# ProPrj_stm32G474_PPO_Display_2026-03-19.net
KiCad netlist of a schematic drawn in EasyEDA Pro
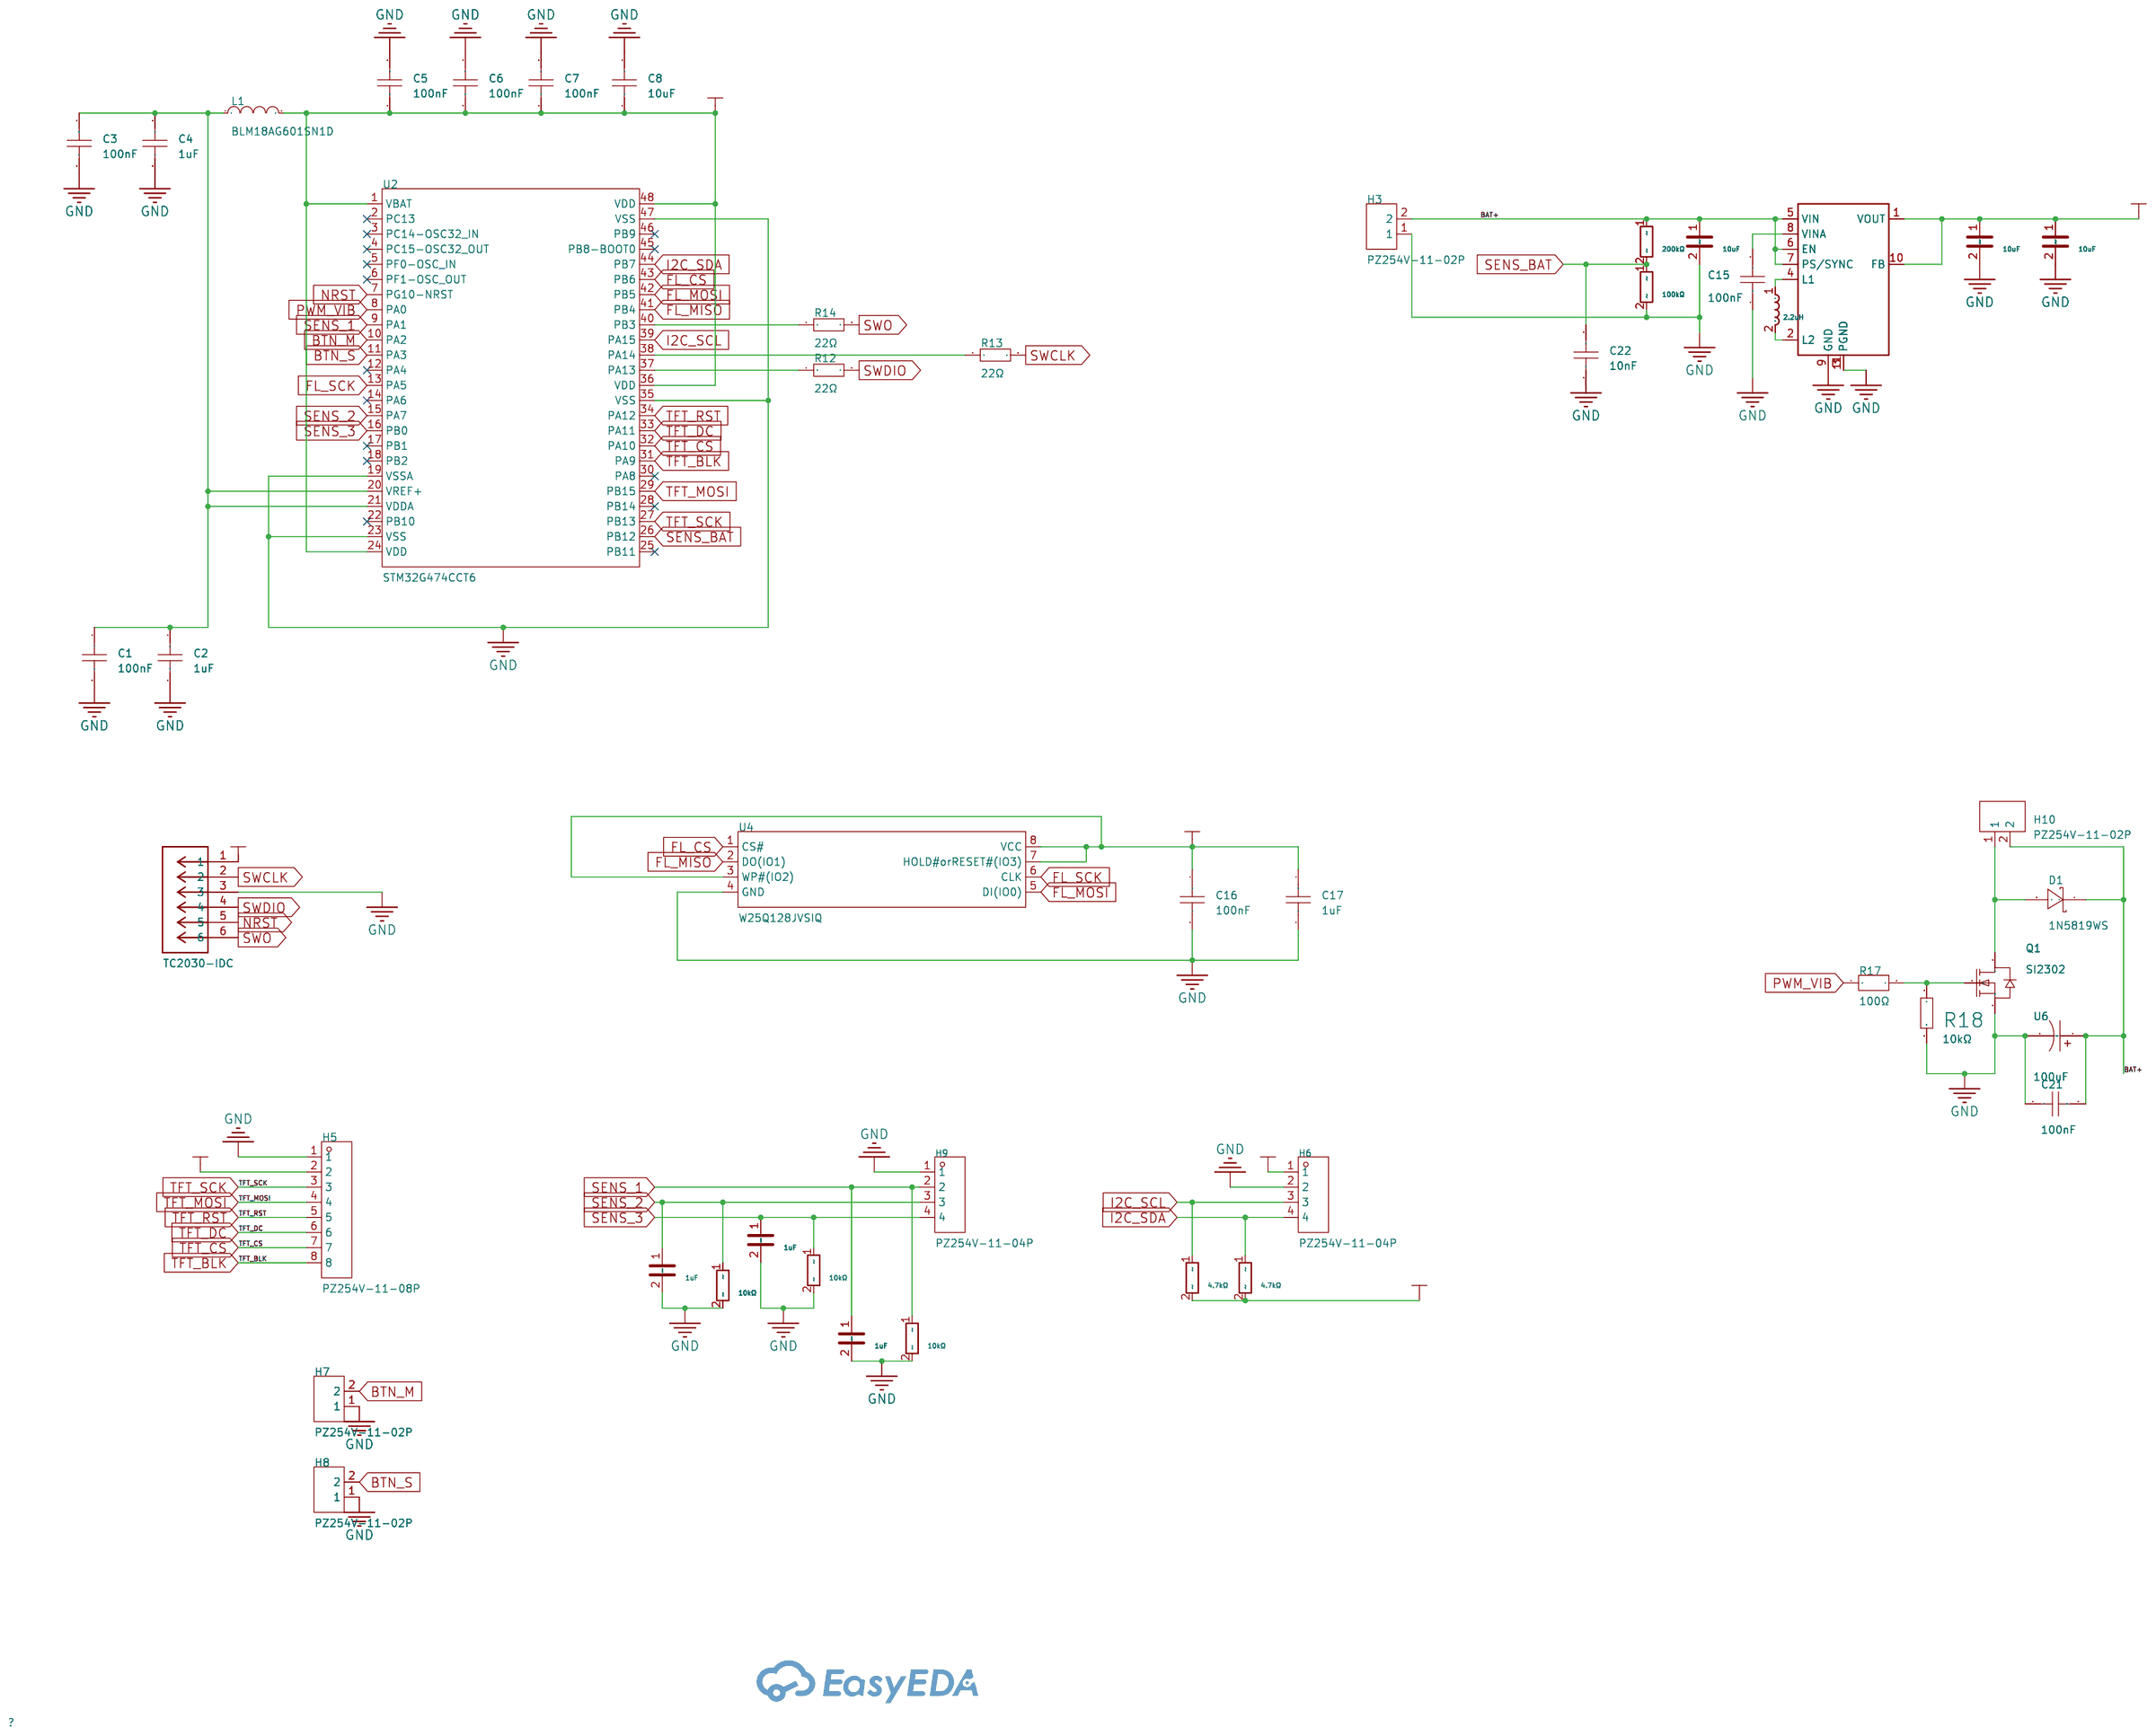
[diagram p0: schematic sheet]

(export (version "E")
  (design (tool "Eeschema 10.0.6"))
  (components
    (comp (ref "C1")
      (value "100nF")
      (footprint "easyedapro:C0603")
      (description "Capacitance:100nF Tolerance:±10% Tolerance:±10% Voltage Rating:50V Temperature Coefficient:X7R")
      (fields
        (field (name "Manufacturer Part") "CC0603KRX7R9BB104")
        (field (name "Manufacturer") "YAGEO(国巨)")
      )
      (libsource (lib "easyedapro") (part "CC0603KRX7R9BB104"))
    )
    (comp (ref "C2")
      (value "1uF")
      (footprint "easyedapro:C0603")
      (description "Capacitance:1uF Tolerance:±10% Tolerance:±10% Voltage Rating:50V Temperature Coefficient:X5R")
      (fields
        (field (name "Manufacturer Part") "CL10A105KB8NNNC")
        (field (name "Manufacturer") "SAMSUNG(三星)")
      )
      (libsource (lib "easyedapro") (part "CL10A105KB8NNNC"))
    )
    (comp (ref "C3")
      (value "100nF")
      (footprint "easyedapro:C0603")
      (description "Capacitance:100nF Tolerance:±10% Tolerance:±10% Voltage Rating:50V Temperature Coefficient:X7R")
      (fields
        (field (name "Manufacturer Part") "CC0603KRX7R9BB104")
        (field (name "Manufacturer") "YAGEO(国巨)")
      )
      (libsource (lib "easyedapro") (part "CC0603KRX7R9BB104"))
    )
    (comp (ref "C4")
      (value "1uF")
      (footprint "easyedapro:C0603")
      (description "Capacitance:1uF Tolerance:±10% Tolerance:±10% Voltage Rating:50V Temperature Coefficient:X5R")
      (fields
        (field (name "Manufacturer Part") "CL10A105KB8NNNC")
        (field (name "Manufacturer") "SAMSUNG(三星)")
      )
      (libsource (lib "easyedapro") (part "CL10A105KB8NNNC"))
    )
    (comp (ref "C5")
      (value "100nF")
      (footprint "easyedapro:C0603")
      (description "Capacitance:100nF Tolerance:±10% Tolerance:±10% Voltage Rating:50V Temperature Coefficient:X7R")
      (fields
        (field (name "Manufacturer Part") "CC0603KRX7R9BB104")
        (field (name "Manufacturer") "YAGEO(国巨)")
      )
      (libsource (lib "easyedapro") (part "CC0603KRX7R9BB104"))
    )
    (comp (ref "C6")
      (value "100nF")
      (footprint "easyedapro:C0603")
      (description "Capacitance:100nF Tolerance:±10% Tolerance:±10% Voltage Rating:50V Temperature Coefficient:X7R")
      (fields
        (field (name "Manufacturer Part") "CC0603KRX7R9BB104")
        (field (name "Manufacturer") "YAGEO(国巨)")
      )
      (libsource (lib "easyedapro") (part "CC0603KRX7R9BB104"))
    )
    (comp (ref "C7")
      (value "100nF")
      (footprint "easyedapro:C0603")
      (description "Capacitance:100nF Tolerance:±10% Tolerance:±10% Voltage Rating:50V Temperature Coefficient:X7R")
      (fields
        (field (name "Manufacturer Part") "CC0603KRX7R9BB104")
        (field (name "Manufacturer") "YAGEO(国巨)")
      )
      (libsource (lib "easyedapro") (part "CC0603KRX7R9BB104"))
    )
    (comp (ref "C8")
      (value "10uF")
      (footprint "easyedapro:C0603")
      (description "Capacitance:10uF Tolerance:±20% Tolerance:±20% Voltage Rating:6.3V Temperature Coefficient:X5R")
      (fields
        (field (name "Manufacturer Part") "CL10A106MQ8NNNC")
        (field (name "Manufacturer") "SAMSUNG(三星)")
      )
      (libsource (lib "easyedapro") (part "CL10A106MQ8NNNC"))
    )
    (comp (ref "C9")
      (value "1uF")
      (footprint "easyedapro:Capacitor_SMD:C_0603_1608Metric")
      (description "Capacitance:1uF Tolerance:±10% Tolerance:±10% Voltage Rating:50V Temperature Coefficient:X7R")
      (fields
        (field (name "Manufacturer Part") "CL10B105KB8NQNC")
        (field (name "Manufacturer") "SAMSUNG(三星)")
      )
      (libsource (lib "easyedapro") (part "Device_C"))
    )
    (comp (ref "C10")
      (value "10uF")
      (footprint "easyedapro:Capacitor_SMD:C_0603_1608Metric")
      (description "Capacitance:10uF Tolerance:±20% Tolerance:±20% Voltage Rating:6.3V Temperature Coefficient:X5R")
      (fields
        (field (name "Manufacturer Part") "CL10A106MQ8NNNC")
        (field (name "Manufacturer") "SAMSUNG(三星)")
      )
      (libsource (lib "easyedapro") (part "Device_C"))
    )
    (comp (ref "C11")
      (value "10uF")
      (footprint "easyedapro:Capacitor_SMD:C_0603_1608Metric")
      (description "Capacitance:10uF Tolerance:±20% Tolerance:±20% Voltage Rating:25V Temperature Coefficient:X5R")
      (fields
        (field (name "Manufacturer Part") "CL10A106MA8NRNC")
        (field (name "Manufacturer") "SAMSUNG(三星)")
      )
      (libsource (lib "easyedapro") (part "Device_C"))
    )
    (comp (ref "C15")
      (value "100nF")
      (footprint "easyedapro:C0603")
      (description "Capacitance:100nF Tolerance:±10% Tolerance:±10% Voltage Rating:50V Temperature Coefficient:X7R")
      (fields
        (field (name "Manufacturer Part") "CC0603KRX7R9BB104")
        (field (name "Manufacturer") "YAGEO(国巨)")
      )
      (libsource (lib "easyedapro") (part "CC0603KRX7R9BB104"))
    )
    (comp (ref "C16")
      (value "100nF")
      (footprint "easyedapro:C0603")
      (description "Capacitance:100nF Tolerance:±10% Tolerance:±10% Voltage Rating:50V Temperature Coefficient:X7R")
      (fields
        (field (name "Manufacturer Part") "CC0603KRX7R9BB104")
        (field (name "Manufacturer") "YAGEO(国巨)")
      )
      (libsource (lib "easyedapro") (part "CC0603KRX7R9BB104"))
    )
    (comp (ref "C17")
      (value "1uF")
      (footprint "easyedapro:C0603")
      (description "Capacitance:1uF Tolerance:±10% Tolerance:±10% Voltage Rating:50V Temperature Coefficient:X5R")
      (fields
        (field (name "Manufacturer Part") "CL10A105KB8NNNC")
        (field (name "Manufacturer") "SAMSUNG(三星)")
      )
      (libsource (lib "easyedapro") (part "CL10A105KB8NNNC"))
    )
    (comp (ref "C18")
      (value "10uF")
      (footprint "easyedapro:Capacitor_SMD:C_0603_1608Metric")
      (description "Capacitance:10uF Tolerance:±20% Tolerance:±20% Voltage Rating:25V Temperature Coefficient:X5R")
      (fields
        (field (name "Manufacturer Part") "CL10A106MA8NRNC")
        (field (name "Manufacturer") "SAMSUNG(三星)")
      )
      (libsource (lib "easyedapro") (part "Device_C"))
    )
    (comp (ref "C19")
      (value "1uF")
      (footprint "easyedapro:Capacitor_SMD:C_0603_1608Metric")
      (description "Capacitance:1uF Tolerance:±10% Tolerance:±10% Voltage Rating:50V Temperature Coefficient:X7R")
      (fields
        (field (name "Manufacturer Part") "CL10B105KB8NQNC")
        (field (name "Manufacturer") "SAMSUNG(三星)")
      )
      (libsource (lib "easyedapro") (part "Device_C"))
    )
    (comp (ref "C20")
      (value "1uF")
      (footprint "easyedapro:Capacitor_SMD:C_0603_1608Metric")
      (description "Capacitance:1uF Tolerance:±10% Tolerance:±10% Voltage Rating:50V Temperature Coefficient:X7R")
      (fields
        (field (name "Manufacturer Part") "CL10B105KB8NQNC")
        (field (name "Manufacturer") "SAMSUNG(三星)")
      )
      (libsource (lib "easyedapro") (part "Device_C"))
    )
    (comp (ref "C21")
      (value "100nF")
      (footprint "easyedapro:C0603")
      (description "Capacitance:100nF Tolerance:±10% Tolerance:±10% Voltage Rating:50V Temperature Coefficient:X7R")
      (fields
        (field (name "Manufacturer Part") "CC0603KRX7R9BB104")
        (field (name "Manufacturer") "YAGEO(国巨)")
      )
      (libsource (lib "easyedapro") (part "CC0603KRX7R9BB104"))
    )
    (comp (ref "C22")
      (value "10nF")
      (footprint "easyedapro:C0603")
      (description "Capacitance:10nF Tolerance:±10% Tolerance:±10% Voltage Rating:50V Temperature Coefficient:X7R")
      (fields
        (field (name "Manufacturer Part") "CL10B103KB8NNNC")
        (field (name "Manufacturer") "SAMSUNG(三星)")
      )
      (libsource (lib "easyedapro") (part "CC0603KRX7R9BB104"))
    )
    (comp (ref "D1")
      (value "1N5819WS")
      (footprint "easyedapro:SOD-323_L1.8-W1.3-LS2.5-RD")
      (fields (field (name "Manufacturer") "Hottech(合科泰)"))
      (libsource (lib "easyedapro") (part "1N5819WS"))
    )
    (comp (ref "H3")
      (value "PZ254V-11-02P")
      (footprint "easyedapro:HDR-TH_2P-P2.54-V-M")
      (fields (field (name "Manufacturer") "XFCN(兴飞)"))
      (libsource (lib "easyedapro") (part "PZ254V-11-02P"))
    )
    (comp (ref "H5")
      (value "PZ254V-11-08P")
      (footprint "easyedapro:HDR-TH_8P-P2.54-V-M")
      (fields (field (name "Manufacturer") "XFCN(兴飞)"))
      (libsource (lib "easyedapro") (part "PZ254V-11-08P"))
    )
    (comp (ref "H6")
      (value "PZ254V-11-04P")
      (footprint "easyedapro:HDR-TH_4P-P2.54-V-M")
      (fields (field (name "Manufacturer") "XFCN(兴飞)"))
      (libsource (lib "easyedapro") (part "PZ254V-11-04P_C2691448"))
    )
    (comp (ref "H7")
      (value "PZ254V-11-02P")
      (footprint "easyedapro:HDR-TH_2P-P2.54-V-M")
      (fields (field (name "Manufacturer") "XFCN(兴飞)"))
      (libsource (lib "easyedapro") (part "PZ254V-11-02P"))
    )
    (comp (ref "H8")
      (value "PZ254V-11-02P")
      (footprint "easyedapro:HDR-TH_2P-P2.54-V-M")
      (fields (field (name "Manufacturer") "XFCN(兴飞)"))
      (libsource (lib "easyedapro") (part "PZ254V-11-02P"))
    )
    (comp (ref "H9")
      (value "PZ254V-11-04P")
      (footprint "easyedapro:HDR-TH_4P-P2.54-V-M")
      (fields (field (name "Manufacturer") "XFCN(兴飞)"))
      (libsource (lib "easyedapro") (part "PZ254V-11-04P_C2691448"))
    )
    (comp (ref "H10")
      (value "PZ254V-11-02P")
      (footprint "easyedapro:HDR-TH_2P-P2.54-V-M")
      (fields (field (name "Manufacturer") "XFCN(兴飞)"))
      (libsource (lib "easyedapro") (part "PZ254V-11-02P"))
    )
    (comp (ref "L1")
      (value "BLM18AG601SN1D")
      (footprint "easyedapro:L0603")
      (fields (field (name "Manufacturer") "muRata(村田)"))
      (libsource (lib "easyedapro") (part "BLM18AG601SN1D"))
    )
    (comp (ref "L2")
      (value "2.2uH")
      (footprint "easyedapro:Inductor_SMD:L_0402_1005Metric")
      (fields (field (name "Manufacturer Part") "LQH3NPN2R2MMEL") (field (name "Manufacturer") "muRata(村田)"))
      (libsource (lib "easyedapro") (part "Device_L"))
    )
    (comp (ref "Q1")
      (value "SI2302")
      (footprint "easyedapro:SOT-23-3_L2.9-W1.3-P1.90-LS2.4-BR")
      (fields (field (name "Manufacturer") "FOSAN(富捷/富信)"))
      (libsource (lib "easyedapro") (part "SI2302_C20628873"))
    )
    (comp (ref "R7")
      (value "200kΩ")
      (footprint "easyedapro:Resistor_SMD:R_0201_0603Metric")
      (fields
        (field (name "Manufacturer Part") "0603WAF2003T5E")
        (field (name "Manufacturer") "UNI-ROYAL(厚声)")
      )
      (libsource (lib "easyedapro") (part "Device_R"))
    )
    (comp (ref "R8")
      (value "100kΩ")
      (footprint "easyedapro:Resistor_SMD:R_0201_0603Metric")
      (fields (field (name "Manufacturer Part") "FRC0603J104 TS") (field (name "Manufacturer") "FOJAN(富捷)"))
      (libsource (lib "easyedapro") (part "Device_R"))
    )
    (comp (ref "R11")
      (value "10kΩ")
      (footprint "easyedapro:Resistor_SMD:R_0201_0603Metric")
      (fields
        (field (name "Manufacturer Part") "0603WAF1002T5E")
        (field (name "Manufacturer") "UNI-ROYAL(厚声)")
      )
      (libsource (lib "easyedapro") (part "Device_R"))
    )
    (comp (ref "R12")
      (value "22Ω")
      (footprint "easyedapro:R0603")
      (fields
        (field (name "Manufacturer Part") "0603WAF220JT5E")
        (field (name "Manufacturer") "UNI-ROYAL(厚声)")
      )
      (libsource (lib "easyedapro") (part "0603WAF220JT5E"))
    )
    (comp (ref "R13")
      (value "22Ω")
      (footprint "easyedapro:R0603")
      (fields
        (field (name "Manufacturer Part") "0603WAF220JT5E")
        (field (name "Manufacturer") "UNI-ROYAL(厚声)")
      )
      (libsource (lib "easyedapro") (part "0603WAF220JT5E"))
    )
    (comp (ref "R14")
      (value "22Ω")
      (footprint "easyedapro:R0603")
      (fields
        (field (name "Manufacturer Part") "0603WAF220JT5E")
        (field (name "Manufacturer") "UNI-ROYAL(厚声)")
      )
      (libsource (lib "easyedapro") (part "0603WAF220JT5E"))
    )
    (comp (ref "R15")
      (value "10kΩ")
      (footprint "easyedapro:Resistor_SMD:R_0201_0603Metric")
      (fields
        (field (name "Manufacturer Part") "0603WAF1002T5E")
        (field (name "Manufacturer") "UNI-ROYAL(厚声)")
      )
      (libsource (lib "easyedapro") (part "Device_R"))
    )
    (comp (ref "R16")
      (value "10kΩ")
      (footprint "easyedapro:Resistor_SMD:R_0201_0603Metric")
      (fields
        (field (name "Manufacturer Part") "0603WAF1002T5E")
        (field (name "Manufacturer") "UNI-ROYAL(厚声)")
      )
      (libsource (lib "easyedapro") (part "Device_R"))
    )
    (comp (ref "R17")
      (value "100Ω")
      (footprint "easyedapro:R0603")
      (fields (field (name "Manufacturer Part") "FRC0603J101 TS") (field (name "Manufacturer") "FOJAN(富捷)"))
      (libsource (lib "easyedapro") (part "FRC0603J101 TS"))
    )
    (comp (ref "R18")
      (value "10kΩ")
      (footprint "easyedapro:R0603")
      (fields
        (field (name "Manufacturer Part") "0603WAF1002T5E")
        (field (name "Manufacturer") "UNI-ROYAL(厚声)")
      )
      (libsource (lib "easyedapro") (part "0603WAF1002T5E"))
    )
    (comp (ref "R19")
      (value "4.7kΩ")
      (footprint "easyedapro:Resistor_SMD:R_0201_0603Metric")
      (fields
        (field (name "Manufacturer Part") "0603WAF4701T5E")
        (field (name "Manufacturer") "UNI-ROYAL(厚声)")
      )
      (libsource (lib "easyedapro") (part "Device_R"))
    )
    (comp (ref "R20")
      (value "4.7kΩ")
      (footprint "easyedapro:Resistor_SMD:R_0201_0603Metric")
      (fields
        (field (name "Manufacturer Part") "0603WAF4701T5E")
        (field (name "Manufacturer") "UNI-ROYAL(厚声)")
      )
      (libsource (lib "easyedapro") (part "Device_R"))
    )
    (comp (ref "U2")
      (value "STM32G474CCT6")
      (footprint "easyedapro:LQFP-48_L7.0-W7.0-P0.50-LS9.0-BL")
      (fields (field (name "Manufacturer") "ST(意法半导体)"))
      (libsource (lib "easyedapro") (part "STM32G474CCT6"))
    )
    (comp (ref "U3")
      (value "TPS63031DSKR")
      (footprint "easyedapro:Package_SON:WSON-10-1EP_2.5x2.5mm_P0.5mm_EP1.2x2mm")
      (fields (field (name "Manufacturer") "TI(德州仪器)"))
      (libsource (lib "easyedapro") (part "Regulator_Switching_TPS63031DSK"))
    )
    (comp (ref "U4")
      (value "W25Q128JVSIQ")
      (footprint "easyedapro:SOIC-8_L5.3-W5.3-P1.27-LS8.0-BL")
      (fields (field (name "Manufacturer") "Winbond(华邦)"))
      (libsource (lib "easyedapro") (part "W25Q128JVSIQ"))
    )
    (comp (ref "U5") (value "TC2030-IDC") (libsource (lib "easyedapro") (part "TC2030-IDC")))
    (comp (ref "U6")
      (value "100uF")
      (footprint "easyedapro:CAP-SMD_BD5.0-L5.3-W5.3-LS6.3-FD")
      (description "Capacitance:100uF Tolerance:±20% Tolerance:±20% Voltage Rating:6.3V Temperature Coefficient:X5R")
      (fields
        (field (name "Manufacturer Part") "CL31A107MQHNNNE")
        (field (name "Manufacturer") "SAMSUNG(三星)")
      )
      (libsource (lib "easyedapro") (part "CK1A101M-CRD54_C3001231"))
    )
  )
  (nets
    (net (code "1") (name "/BAT+") (class "Default")
      (node (ref "C10") (pin "1") (pinfunction "~_1") (pintype "unspecified"))
      (node (ref "C21") (pin "2") (pinfunction "2_2") (pintype "unspecified"))
      (node (ref "D1") (pin "1") (pinfunction "K_1") (pintype "unspecified"))
      (node (ref "H10") (pin "2") (pinfunction "2_2") (pintype "unspecified"))
      (node (ref "H3") (pin "2") (pinfunction "2_2") (pintype "unspecified"))
      (node (ref "R7") (pin "1") (pinfunction "~_1") (pintype "unspecified"))
      (node (ref "U3") (pin "5") (pinfunction "VIN_5") (pintype "unspecified"))
      (node (ref "U3") (pin "6") (pinfunction "EN_6") (pintype "input"))
      (node (ref "U3") (pin "7") (pinfunction "PS/SYNC_7") (pintype "input"))
      (node (ref "U6") (pin "1") (pinfunction "1_1") (pintype "unspecified"))
    )
    (net (code "2") (name "BTN_M") (class "Default")
      (node (ref "H7") (pin "2") (pinfunction "2_2") (pintype "unspecified"))
      (node (ref "U2") (pin "10") (pinfunction "PA2_10") (pintype "unspecified"))
    )
    (net (code "3") (name "BTN_S") (class "Default")
      (node (ref "H8") (pin "2") (pinfunction "2_2") (pintype "unspecified"))
      (node (ref "U2") (pin "11") (pinfunction "PA3_11") (pintype "unspecified"))
    )
    (net (code "4") (name "FL_CS") (class "Default")
      (node (ref "U2") (pin "43") (pinfunction "PB6_43") (pintype "unspecified"))
      (node (ref "U4") (pin "1") (pinfunction "CS#_1") (pintype "unspecified"))
    )
    (net (code "5") (name "FL_MISO") (class "Default")
      (node (ref "U2") (pin "41") (pinfunction "PB4_41") (pintype "unspecified"))
      (node (ref "U4") (pin "2") (pinfunction "DO(IO1)_2") (pintype "unspecified"))
    )
    (net (code "6") (name "FL_MOSI") (class "Default")
      (node (ref "U2") (pin "42") (pinfunction "PB5_42") (pintype "unspecified"))
      (node (ref "U4") (pin "5") (pinfunction "DI(IO0)_5") (pintype "unspecified"))
    )
    (net (code "7") (name "FL_SCK") (class "Default")
      (node (ref "U2") (pin "13") (pinfunction "PA5_13") (pintype "unspecified"))
      (node (ref "U4") (pin "6") (pinfunction "CLK_6") (pintype "unspecified"))
    )
    (net (code "8") (name "GND") (class "Default")
      (node (ref "C1") (pin "2") (pinfunction "2_2") (pintype "unspecified"))
      (node (ref "C10") (pin "2") (pinfunction "~_2") (pintype "unspecified"))
      (node (ref "C11") (pin "2") (pinfunction "~_2") (pintype "unspecified"))
      (node (ref "C15") (pin "1") (pinfunction "1_1") (pintype "unspecified"))
      (node (ref "C16") (pin "2") (pinfunction "2_2") (pintype "unspecified"))
      (node (ref "C17") (pin "2") (pinfunction "2_2") (pintype "unspecified"))
      (node (ref "C18") (pin "2") (pinfunction "~_2") (pintype "unspecified"))
      (node (ref "C19") (pin "2") (pinfunction "~_2") (pintype "unspecified"))
      (node (ref "C2") (pin "2") (pinfunction "2_2") (pintype "unspecified"))
      (node (ref "C20") (pin "2") (pinfunction "~_2") (pintype "unspecified"))
      (node (ref "C21") (pin "1") (pinfunction "1_1") (pintype "unspecified"))
      (node (ref "C22") (pin "1") (pinfunction "1_1") (pintype "unspecified"))
      (node (ref "C3") (pin "2") (pinfunction "2_2") (pintype "unspecified"))
      (node (ref "C4") (pin "2") (pinfunction "2_2") (pintype "unspecified"))
      (node (ref "C5") (pin "1") (pinfunction "1_1") (pintype "unspecified"))
      (node (ref "C6") (pin "1") (pinfunction "1_1") (pintype "unspecified"))
      (node (ref "C7") (pin "1") (pinfunction "1_1") (pintype "unspecified"))
      (node (ref "C8") (pin "1") (pinfunction "1_1") (pintype "unspecified"))
      (node (ref "C9") (pin "2") (pinfunction "~_2") (pintype "unspecified"))
      (node (ref "H3") (pin "1") (pinfunction "1_1") (pintype "unspecified"))
      (node (ref "H5") (pin "1") (pinfunction "1_1") (pintype "unspecified"))
      (node (ref "H6") (pin "2") (pinfunction "2_2") (pintype "input"))
      (node (ref "H7") (pin "1") (pinfunction "1_1") (pintype "unspecified"))
      (node (ref "H8") (pin "1") (pinfunction "1_1") (pintype "unspecified"))
      (node (ref "H9") (pin "1") (pinfunction "1_1") (pintype "input"))
      (node (ref "Q1") (pin "2") (pinfunction "S_2") (pintype "unspecified"))
      (node (ref "R11") (pin "2") (pinfunction "~_2") (pintype "unspecified"))
      (node (ref "R15") (pin "2") (pinfunction "~_2") (pintype "unspecified"))
      (node (ref "R16") (pin "2") (pinfunction "~_2") (pintype "unspecified"))
      (node (ref "R18") (pin "2") (pinfunction "2_2") (pintype "input"))
      (node (ref "R8") (pin "2") (pinfunction "~_2") (pintype "unspecified"))
      (node (ref "U2") (pin "19") (pinfunction "VSSA_19") (pintype "unspecified"))
      (node (ref "U2") (pin "23") (pinfunction "VSS_23") (pintype "unspecified"))
      (node (ref "U2") (pin "35") (pinfunction "VSS_35") (pintype "unspecified"))
      (node (ref "U2") (pin "47") (pinfunction "VSS_47") (pintype "unspecified"))
      (node (ref "U3") (pin "11") (pinfunction "PGND_11") (pintype "unspecified"))
      (node (ref "U3") (pin "3") (pinfunction "PGND_3") (pintype "unspecified"))
      (node (ref "U3") (pin "9") (pinfunction "GND_9") (pintype "unspecified"))
      (node (ref "U4") (pin "4") (pinfunction "GND_4") (pintype "unspecified"))
      (node (ref "U5") (pin "3") (pinfunction "3_3") (pintype "unspecified"))
      (node (ref "U6") (pin "2") (pinfunction "2_2") (pintype "unspecified"))
    )
    (net (code "9") (name "I2C_SCL") (class "Default")
      (node (ref "H6") (pin "3") (pinfunction "3_3") (pintype "input"))
      (node (ref "R19") (pin "1") (pinfunction "~_1") (pintype "unspecified"))
      (node (ref "U2") (pin "39") (pinfunction "PA15_39") (pintype "unspecified"))
    )
    (net (code "10") (name "I2C_SDA") (class "Default")
      (node (ref "H6") (pin "4") (pinfunction "4_4") (pintype "input"))
      (node (ref "R20") (pin "1") (pinfunction "~_1") (pintype "unspecified"))
      (node (ref "U2") (pin "44") (pinfunction "PB7_44") (pintype "unspecified"))
    )
    (net (code "11") (name "NRST") (class "Default")
      (node (ref "U2") (pin "7") (pinfunction "PG10-NRST_7") (pintype "unspecified"))
      (node (ref "U5") (pin "5") (pinfunction "5_5") (pintype "unspecified"))
    )
    (net (code "12") (name "Net-(D1-A)") (class "Default")
      (node (ref "D1") (pin "2") (pinfunction "A_2") (pintype "unspecified"))
      (node (ref "H10") (pin "1") (pinfunction "1_1") (pintype "unspecified"))
      (node (ref "Q1") (pin "3") (pinfunction "D_3") (pintype "unspecified"))
    )
    (net (code "13") (name "Net-(Q1-G)") (class "Default")
      (node (ref "Q1") (pin "1") (pinfunction "G_1") (pintype "unspecified"))
      (node (ref "R17") (pin "2") (pinfunction "2_2") (pintype "unspecified"))
      (node (ref "R18") (pin "1") (pinfunction "1_1") (pintype "input"))
    )
    (net (code "14") (name "Net-(U2-PA13)") (class "Default")
      (node (ref "R12") (pin "1") (pinfunction "1_1") (pintype "input"))
      (node (ref "U2") (pin "37") (pinfunction "PA13_37") (pintype "unspecified"))
    )
    (net (code "15") (name "Net-(U2-PA14)") (class "Default")
      (node (ref "R13") (pin "1") (pinfunction "1_1") (pintype "input"))
      (node (ref "U2") (pin "38") (pinfunction "PA14_38") (pintype "unspecified"))
    )
    (net (code "16") (name "Net-(U2-PB3)") (class "Default")
      (node (ref "R14") (pin "1") (pinfunction "1_1") (pintype "input"))
      (node (ref "U2") (pin "40") (pinfunction "PB3_40") (pintype "unspecified"))
    )
    (net (code "17") (name "Net-(U2-VDDA)") (class "Default")
      (node (ref "C1") (pin "1") (pinfunction "1_1") (pintype "unspecified"))
      (node (ref "C2") (pin "1") (pinfunction "1_1") (pintype "unspecified"))
      (node (ref "C3") (pin "1") (pinfunction "1_1") (pintype "unspecified"))
      (node (ref "C4") (pin "1") (pinfunction "1_1") (pintype "unspecified"))
      (node (ref "L1") (pin "1") (pinfunction "1_1") (pintype "unspecified"))
      (node (ref "U2") (pin "20") (pinfunction "VREF+_20") (pintype "unspecified"))
      (node (ref "U2") (pin "21") (pinfunction "VDDA_21") (pintype "unspecified"))
    )
    (net (code "18") (name "Net-(U3-L1)") (class "Default")
      (node (ref "L2") (pin "1") (pinfunction "1_1") (pintype "unspecified"))
      (node (ref "U3") (pin "4") (pinfunction "L1_4") (pintype "input"))
    )
    (net (code "19") (name "Net-(U3-L2)") (class "Default")
      (node (ref "L2") (pin "2") (pinfunction "2_2") (pintype "unspecified"))
      (node (ref "U3") (pin "2") (pinfunction "L2_2") (pintype "input"))
    )
    (net (code "20") (name "Net-(U3-VINA)") (class "Default")
      (node (ref "C15") (pin "2") (pinfunction "2_2") (pintype "unspecified"))
      (node (ref "U3") (pin "8") (pinfunction "VINA_8") (pintype "unspecified"))
    )
    (net (code "21") (name "PWM_VIB") (class "Default")
      (node (ref "R17") (pin "1") (pinfunction "1_1") (pintype "unspecified"))
      (node (ref "U2") (pin "8") (pinfunction "PA0_8") (pintype "unspecified"))
    )
    (net (code "22") (name "SENS_1") (class "Default")
      (node (ref "C9") (pin "1") (pinfunction "~_1") (pintype "unspecified"))
      (node (ref "H9") (pin "2") (pinfunction "2_2") (pintype "input"))
      (node (ref "R16") (pin "1") (pinfunction "~_1") (pintype "unspecified"))
      (node (ref "U2") (pin "9") (pinfunction "PA1_9") (pintype "unspecified"))
    )
    (net (code "23") (name "SENS_2") (class "Default")
      (node (ref "C19") (pin "1") (pinfunction "~_1") (pintype "unspecified"))
      (node (ref "H9") (pin "3") (pinfunction "3_3") (pintype "input"))
      (node (ref "R11") (pin "1") (pinfunction "~_1") (pintype "unspecified"))
      (node (ref "U2") (pin "15") (pinfunction "PA7_15") (pintype "unspecified"))
    )
    (net (code "24") (name "SENS_3") (class "Default")
      (node (ref "C20") (pin "1") (pinfunction "~_1") (pintype "unspecified"))
      (node (ref "H9") (pin "4") (pinfunction "4_4") (pintype "input"))
      (node (ref "R15") (pin "1") (pinfunction "~_1") (pintype "unspecified"))
      (node (ref "U2") (pin "16") (pinfunction "PB0_16") (pintype "unspecified"))
    )
    (net (code "25") (name "SENS_BAT") (class "Default")
      (node (ref "C22") (pin "2") (pinfunction "2_2") (pintype "unspecified"))
      (node (ref "R7") (pin "2") (pinfunction "~_2") (pintype "unspecified"))
      (node (ref "R8") (pin "1") (pinfunction "~_1") (pintype "unspecified"))
      (node (ref "U2") (pin "26") (pinfunction "PB12_26") (pintype "unspecified"))
    )
    (net (code "26") (name "SWCLK") (class "Default")
      (node (ref "R13") (pin "2") (pinfunction "2_2") (pintype "input"))
      (node (ref "U5") (pin "2") (pinfunction "2_2") (pintype "unspecified"))
    )
    (net (code "27") (name "SWDIO") (class "Default")
      (node (ref "R12") (pin "2") (pinfunction "2_2") (pintype "input"))
      (node (ref "U5") (pin "4") (pinfunction "4_4") (pintype "unspecified"))
    )
    (net (code "28") (name "SWO") (class "Default")
      (node (ref "R14") (pin "2") (pinfunction "2_2") (pintype "input"))
      (node (ref "U5") (pin "6") (pinfunction "6_6") (pintype "unspecified"))
    )
    (net (code "29") (name "TFT_BLK") (class "Default")
      (node (ref "H5") (pin "8") (pinfunction "8_8") (pintype "unspecified"))
      (node (ref "U2") (pin "31") (pinfunction "PA9_31") (pintype "unspecified"))
    )
    (net (code "30") (name "TFT_CS") (class "Default")
      (node (ref "H5") (pin "7") (pinfunction "7_7") (pintype "unspecified"))
      (node (ref "U2") (pin "32") (pinfunction "PA10_32") (pintype "unspecified"))
    )
    (net (code "31") (name "TFT_DC") (class "Default")
      (node (ref "H5") (pin "6") (pinfunction "6_6") (pintype "unspecified"))
      (node (ref "U2") (pin "33") (pinfunction "PA11_33") (pintype "unspecified"))
    )
    (net (code "32") (name "TFT_MOSI") (class "Default")
      (node (ref "H5") (pin "4") (pinfunction "4_4") (pintype "unspecified"))
      (node (ref "U2") (pin "29") (pinfunction "PB15_29") (pintype "unspecified"))
    )
    (net (code "33") (name "TFT_RST") (class "Default")
      (node (ref "H5") (pin "5") (pinfunction "5_5") (pintype "unspecified"))
      (node (ref "U2") (pin "34") (pinfunction "PA12_34") (pintype "unspecified"))
    )
    (net (code "34") (name "TFT_SCK") (class "Default")
      (node (ref "H5") (pin "3") (pinfunction "3_3") (pintype "unspecified"))
      (node (ref "U2") (pin "27") (pinfunction "PB13_27") (pintype "unspecified"))
    )
    (net (code "35") (name "VDD") (class "Default")
      (node (ref "C11") (pin "1") (pinfunction "~_1") (pintype "unspecified"))
      (node (ref "C16") (pin "1") (pinfunction "1_1") (pintype "unspecified"))
      (node (ref "C17") (pin "1") (pinfunction "1_1") (pintype "unspecified"))
      (node (ref "C18") (pin "1") (pinfunction "~_1") (pintype "unspecified"))
      (node (ref "C5") (pin "2") (pinfunction "2_2") (pintype "unspecified"))
      (node (ref "C6") (pin "2") (pinfunction "2_2") (pintype "unspecified"))
      (node (ref "C7") (pin "2") (pinfunction "2_2") (pintype "unspecified"))
      (node (ref "C8") (pin "2") (pinfunction "2_2") (pintype "unspecified"))
      (node (ref "H5") (pin "2") (pinfunction "2_2") (pintype "unspecified"))
      (node (ref "H6") (pin "1") (pinfunction "1_1") (pintype "input"))
      (node (ref "L1") (pin "2") (pinfunction "2_2") (pintype "unspecified"))
      (node (ref "R19") (pin "2") (pinfunction "~_2") (pintype "unspecified"))
      (node (ref "R20") (pin "2") (pinfunction "~_2") (pintype "unspecified"))
      (node (ref "U2") (pin "1") (pinfunction "VBAT_1") (pintype "unspecified"))
      (node (ref "U2") (pin "24") (pinfunction "VDD_24") (pintype "unspecified"))
      (node (ref "U2") (pin "36") (pinfunction "VDD_36") (pintype "unspecified"))
      (node (ref "U2") (pin "48") (pinfunction "VDD_48") (pintype "unspecified"))
      (node (ref "U3") (pin "1") (pinfunction "VOUT_1") (pintype "unspecified"))
      (node (ref "U3") (pin "10") (pinfunction "FB_10") (pintype "input"))
      (node (ref "U4") (pin "3") (pinfunction "WP#(IO2)_3") (pintype "unspecified"))
      (node (ref "U4") (pin "7") (pinfunction "HOLD#orRESET#(IO3)_7") (pintype "unspecified"))
      (node (ref "U4") (pin "8") (pinfunction "VCC_8") (pintype "unspecified"))
      (node (ref "U5") (pin "1") (pinfunction "1_1") (pintype "unspecified"))
    )
    (net (code "36") (name "unconnected-(U2-PA4-Pad12)") (class "Default")
      (node (ref "U2") (pin "12") (pinfunction "PA4_12") (pintype "unspecified+no_connect"))
    )
    (net (code "37") (name "unconnected-(U2-PA6-Pad14)") (class "Default")
      (node (ref "U2") (pin "14") (pinfunction "PA6_14") (pintype "unspecified+no_connect"))
    )
    (net (code "38") (name "unconnected-(U2-PA8-Pad30)") (class "Default")
      (node (ref "U2") (pin "30") (pinfunction "PA8_30") (pintype "unspecified+no_connect"))
    )
    (net (code "39") (name "unconnected-(U2-PB1-Pad17)") (class "Default")
      (node (ref "U2") (pin "17") (pinfunction "PB1_17") (pintype "unspecified+no_connect"))
    )
    (net (code "40") (name "unconnected-(U2-PB2-Pad18)") (class "Default")
      (node (ref "U2") (pin "18") (pinfunction "PB2_18") (pintype "unspecified+no_connect"))
    )
    (net (code "41") (name "unconnected-(U2-PB8-BOOT0-Pad45)") (class "Default")
      (node (ref "U2") (pin "45") (pinfunction "PB8-BOOT0_45") (pintype "unspecified+no_connect"))
    )
    (net (code "42") (name "unconnected-(U2-PB9-Pad46)") (class "Default")
      (node (ref "U2") (pin "46") (pinfunction "PB9_46") (pintype "unspecified+no_connect"))
    )
    (net (code "43") (name "unconnected-(U2-PB10-Pad22)") (class "Default")
      (node (ref "U2") (pin "22") (pinfunction "PB10_22") (pintype "unspecified+no_connect"))
    )
    (net (code "44") (name "unconnected-(U2-PB11-Pad25)") (class "Default")
      (node (ref "U2") (pin "25") (pinfunction "PB11_25") (pintype "unspecified+no_connect"))
    )
    (net (code "45") (name "unconnected-(U2-PB14-Pad28)") (class "Default")
      (node (ref "U2") (pin "28") (pinfunction "PB14_28") (pintype "unspecified+no_connect"))
    )
    (net (code "46") (name "unconnected-(U2-PC13-Pad2)") (class "Default")
      (node (ref "U2") (pin "2") (pinfunction "PC13_2") (pintype "unspecified+no_connect"))
    )
    (net (code "47") (name "unconnected-(U2-PC14-OSC32_IN-Pad3)") (class "Default")
      (node (ref "U2") (pin "3") (pinfunction "PC14-OSC32_IN_3") (pintype "unspecified+no_connect"))
    )
    (net (code "48") (name "unconnected-(U2-PC15-OSC32_OUT-Pad4)") (class "Default")
      (node (ref "U2") (pin "4") (pinfunction "PC15-OSC32_OUT_4") (pintype "unspecified+no_connect"))
    )
    (net (code "49") (name "unconnected-(U2-PF0-OSC_IN-Pad5)") (class "Default")
      (node (ref "U2") (pin "5") (pinfunction "PF0-OSC_IN_5") (pintype "unspecified+no_connect"))
    )
    (net (code "50") (name "unconnected-(U2-PF1-OSC_OUT-Pad6)") (class "Default")
      (node (ref "U2") (pin "6") (pinfunction "PF1-OSC_OUT_6") (pintype "unspecified+no_connect"))
    )
  )
)
